# COMMUNICATION.net
KiCad netlist of a schematic drawn in Altium Designer
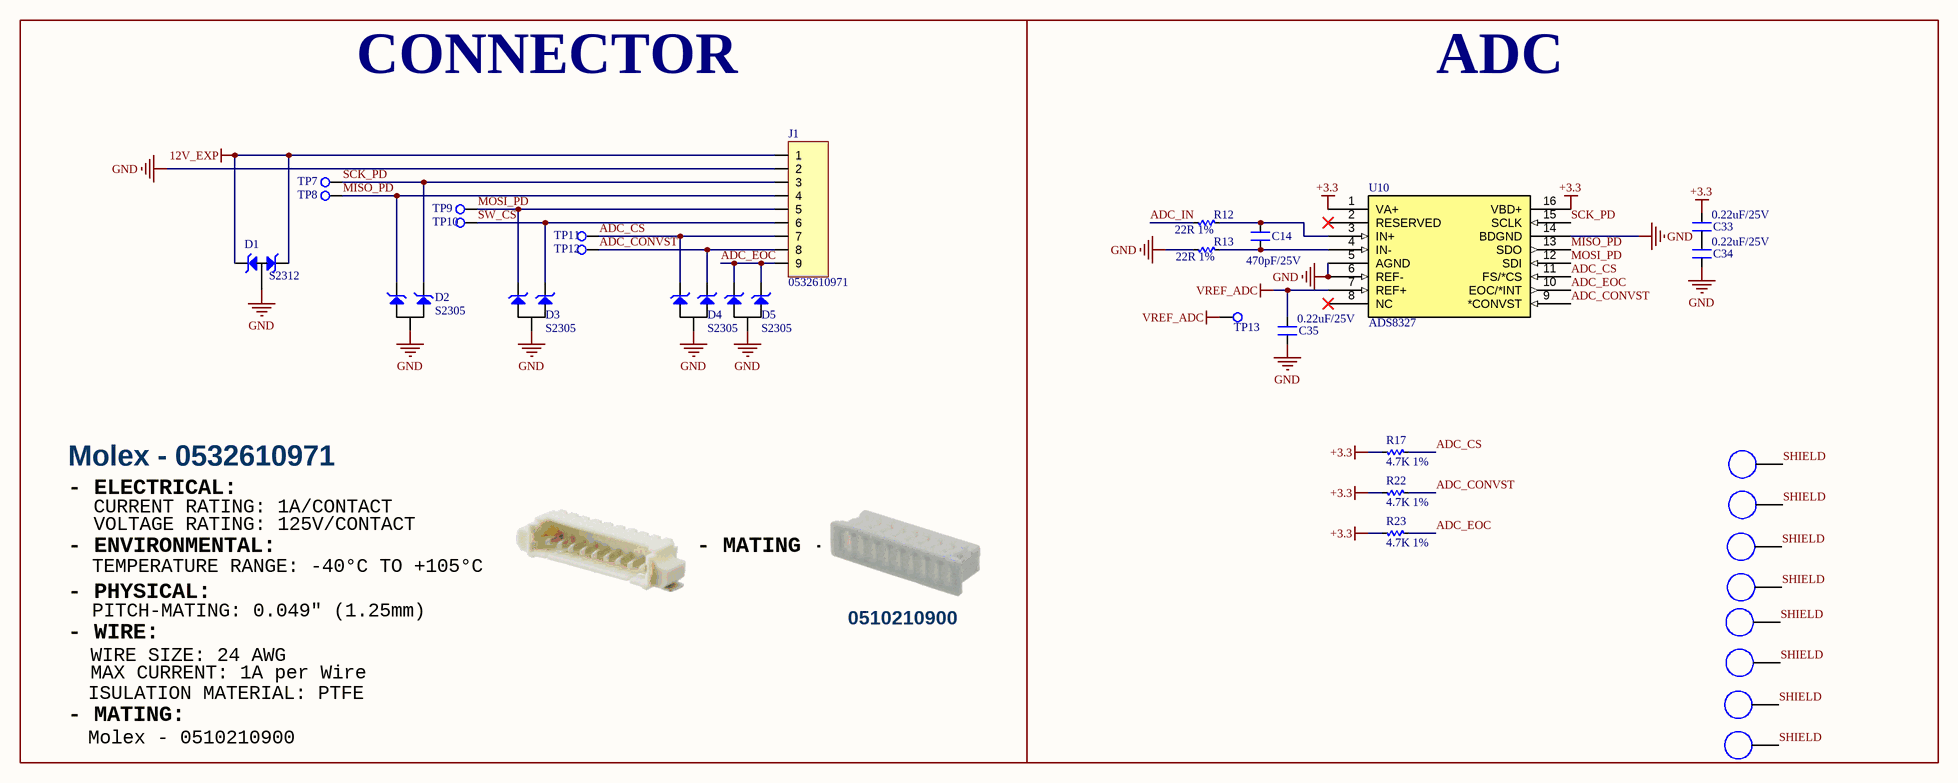
[diagram p0: COMMUNICATION.SchDoc]

(export (version "E")
  (design (tool "Eeschema 10.0.6"))
  (components
    (comp (ref "C14")
      (value "470pF/25V")
      (footprint "CN-SMD-0603")
      (description "0603")
      (libsource (lib "Capacitors") (part "CM"))
    )
    (comp (ref "C33")
      (value "0.22uF/25V")
      (footprint "CN-SMD-0603")
      (description "0603")
      (libsource (lib "Capacitors") (part "CM"))
    )
    (comp (ref "C34")
      (value "0.22uF/25V")
      (footprint "CN-SMD-0603")
      (description "0603")
      (libsource (lib "Capacitors") (part "CM"))
    )
    (comp (ref "C35")
      (value "0.22uF/25V")
      (footprint "CN-SMD-0603")
      (description "0603")
      (libsource (lib "Capacitors") (part "CM"))
    )
    (comp (ref "D1")
      (value "S2312")
      (footprint "SOT23-123")
      (description "TVS DIODE 12VWM 19VC SOT23, P/N:  S2312")
      (libsource (lib "Library") (part "S2315"))
    )
    (comp (ref "D2")
      (value "S2305")
      (footprint "SOT23-123")
      (description "TVS DIODE 5VWM 10.8VC SOT23, P/N:  \r\nS2305")
      (libsource (lib "Library") (part "S2303"))
    )
    (comp (ref "D3")
      (value "S2305")
      (footprint "SOT23-123")
      (description "TVS DIODE 5VWM 10.8VC SOT23, P/N:  \r\nS2305")
      (libsource (lib "Library") (part "S2303"))
    )
    (comp (ref "D4")
      (value "S2305")
      (footprint "SOT23-123")
      (description "TVS DIODE 5VWM 10.8VC SOT23, P/N:  \r\nS2305")
      (libsource (lib "Library") (part "S2303"))
    )
    (comp (ref "D5")
      (value "S2305")
      (footprint "SOT23-123")
      (description "TVS DIODE 5VWM 10.8VC SOT23, P/N:  \r\nS2305")
      (libsource (lib "Library") (part "S2303"))
    )
    (comp (ref "H1") (value "HOLD") (footprint "M3 - 6mm") (libsource (lib "Library_HUNG") (part "PAD_HOLD")))
    (comp (ref "H2") (value "HOLD") (footprint "M3 - 6mm") (libsource (lib "Library_HUNG") (part "PAD_HOLD")))
    (comp (ref "H3") (value "HOLD") (footprint "M3 - 6mm") (libsource (lib "Library_HUNG") (part "PAD_HOLD")))
    (comp (ref "H4") (value "HOLD") (footprint "M3 - 6mm") (libsource (lib "Library_HUNG") (part "PAD_HOLD")))
    (comp (ref "H5") (value "HOLD") (footprint "M3 - 6mm") (libsource (lib "Library_HUNG") (part "PAD_HOLD")))
    (comp (ref "H6") (value "HOLD") (footprint "M3 - 6mm") (libsource (lib "Library_HUNG") (part "PAD_HOLD")))
    (comp (ref "H7") (value "HOLD") (footprint "M3 - 6mm") (libsource (lib "Library_HUNG") (part "PAD_HOLD")))
    (comp (ref "H8") (value "HOLD") (footprint "M3 - 6mm") (libsource (lib "Library_HUNG") (part "PAD_HOLD")))
    (comp (ref "J1")
      (value "0532610971")
      (footprint "0532610971")
      (description "WR-PHD 2.54 mm Angled Socket Header")
      (fields
        (field (name "MANUFACTURER") "Würth Elektronik eiSos GmbH")
        (field (name "PARTNO") "613009143121")
        (field (name "CREATED BY") "Karrer Zheng")
      )
      (libsource (lib "Library") (part "JP9"))
    )
    (comp (ref "R12")
      (value "22R 1%")
      (footprint "RES-SMD-0603")
      (description "0603")
      (fields
        (field (name "MANUFACTURER") "Generic Components")
        (field (name "PUBLISHER") "Altium Hobart Technology Centre")
      )
      (libsource (lib "Library") (part "Res-SMD"))
    )
    (comp (ref "R13")
      (value "22R 1%")
      (footprint "RES-SMD-0603")
      (description "0603")
      (fields
        (field (name "MANUFACTURER") "Generic Components")
        (field (name "PUBLISHER") "Altium Hobart Technology Centre")
      )
      (libsource (lib "Library") (part "Res-SMD"))
    )
    (comp (ref "R17")
      (value "4.7K 1%")
      (footprint "RES-SMD-0603")
      (description "0603")
      (fields
        (field (name "MANUFACTURER") "Generic Components")
        (field (name "PUBLISHER") "Altium Hobart Technology Centre")
      )
      (libsource (lib "Library") (part "Res-SMD"))
    )
    (comp (ref "R22")
      (value "4.7K 1%")
      (footprint "RES-SMD-0603")
      (description "0603")
      (fields
        (field (name "MANUFACTURER") "Generic Components")
        (field (name "PUBLISHER") "Altium Hobart Technology Centre")
      )
      (libsource (lib "Library") (part "Res-SMD"))
    )
    (comp (ref "R23")
      (value "4.7K 1%")
      (footprint "RES-SMD-0603")
      (description "0603")
      (fields
        (field (name "MANUFACTURER") "Generic Components")
        (field (name "PUBLISHER") "Altium Hobart Technology Centre")
      )
      (libsource (lib "Library") (part "Res-SMD"))
    )
    (comp (ref "TP7")
      (value "Test_Point")
      (footprint "TESTPOINT")
      (libsource (lib "Library_HUNG") (part "Test_Point"))
    )
    (comp (ref "TP8")
      (value "Test_Point")
      (footprint "TESTPOINT")
      (libsource (lib "Library_HUNG") (part "Test_Point"))
    )
    (comp (ref "TP9")
      (value "Test_Point")
      (footprint "TESTPOINT")
      (libsource (lib "Library_HUNG") (part "Test_Point"))
    )
    (comp (ref "TP10")
      (value "Test_Point")
      (footprint "TESTPOINT")
      (libsource (lib "Library_HUNG") (part "Test_Point"))
    )
    (comp (ref "TP11")
      (value "Test_Point")
      (footprint "TESTPOINT")
      (libsource (lib "Library_HUNG") (part "Test_Point"))
    )
    (comp (ref "TP12")
      (value "Test_Point")
      (footprint "TESTPOINT")
      (libsource (lib "Library_HUNG") (part "Test_Point"))
    )
    (comp (ref "TP13")
      (value "Test_Point")
      (footprint "TESTPOINT")
      (libsource (lib "Library_HUNG") (part "Test_Point"))
    )
    (comp (ref "U10")
      (value "ADS8327")
      (footprint "TSSOP16")
      (description "IC ADC 16BIT SAR 16TSSOP")
      (libsource (lib "Library") (part "ADS8327"))
    )
  )
  (nets
    (net (code "1") (name "+3.3") (class "Default")
      (node (ref "C33") (pin "2") (pinfunction "2_2") (pintype "passive"))
      (node (ref "R17") (pin "2") (pinfunction "2_2") (pintype "passive"))
      (node (ref "R22") (pin "2") (pinfunction "2_2") (pintype "passive"))
      (node (ref "R23") (pin "2") (pinfunction "2_2") (pintype "passive"))
      (node (ref "U10") (pin "1") (pinfunction "VA+_1") (pintype "power_in"))
      (node (ref "U10") (pin "16") (pinfunction "VBD+_16") (pintype "power_in"))
    )
    (net (code "2") (name "/ADC_CONVST") (class "Default")
      (node (ref "D4") (pin "3") (pintype "passive"))
      (node (ref "J1") (pin "8") (pinfunction "8_8") (pintype "passive"))
      (node (ref "R22") (pin "1") (pinfunction "1_1") (pintype "passive"))
      (node (ref "TP12") (pin "1") (pintype "power_in"))
      (node (ref "U10") (pin "9") (pinfunction "*CONVST_9") (pintype "input"))
    )
    (net (code "3") (name "/ADC_CS") (class "Default")
      (node (ref "D4") (pin "1") (pintype "passive"))
      (node (ref "J1") (pin "7") (pinfunction "7_7") (pintype "passive"))
      (node (ref "R17") (pin "1") (pinfunction "1_1") (pintype "passive"))
      (node (ref "TP11") (pin "1") (pintype "power_in"))
      (node (ref "U10") (pin "11") (pinfunction "FS/*CS_11") (pintype "input"))
    )
    (net (code "4") (name "/ADC_EOC") (class "Default")
      (node (ref "D5") (pin "1") (pintype "passive"))
      (node (ref "D5") (pin "3") (pintype "passive"))
      (node (ref "J1") (pin "9") (pinfunction "9_9") (pintype "passive"))
      (node (ref "R23") (pin "1") (pinfunction "1_1") (pintype "passive"))
      (node (ref "U10") (pin "10") (pinfunction "EOC/*INT_10") (pintype "output"))
    )
    (net (code "5") (name "/ADC_IN") (class "Default")
      (node (ref "R12") (pin "2") (pinfunction "2_2") (pintype "passive"))
    )
    (net (code "6") (name "/MISO_PD") (class "Default")
      (node (ref "D2") (pin "3") (pintype "passive"))
      (node (ref "J1") (pin "4") (pinfunction "4_4") (pintype "passive"))
      (node (ref "TP8") (pin "1") (pintype "power_in"))
      (node (ref "U10") (pin "13") (pinfunction "SDO_13") (pintype "output"))
    )
    (net (code "7") (name "/MOSI_PD") (class "Default")
      (node (ref "D3") (pin "1") (pintype "passive"))
      (node (ref "J1") (pin "5") (pinfunction "5_5") (pintype "passive"))
      (node (ref "TP9") (pin "1") (pintype "power_in"))
      (node (ref "U10") (pin "12") (pinfunction "SDI_12") (pintype "input"))
    )
    (net (code "8") (name "/SCK_PD") (class "Default")
      (node (ref "D2") (pin "1") (pintype "passive"))
      (node (ref "J1") (pin "3") (pinfunction "3_3") (pintype "passive"))
      (node (ref "TP7") (pin "1") (pintype "power_in"))
      (node (ref "U10") (pin "15") (pinfunction "SCLK_15") (pintype "input"))
    )
    (net (code "9") (name "/SHIELD") (class "Default")
      (node (ref "H1") (pin "1") (pintype "power_in"))
      (node (ref "H2") (pin "1") (pintype "power_in"))
      (node (ref "H3") (pin "1") (pintype "power_in"))
      (node (ref "H4") (pin "1") (pintype "power_in"))
      (node (ref "H5") (pin "1") (pintype "power_in"))
      (node (ref "H6") (pin "1") (pintype "power_in"))
      (node (ref "H7") (pin "1") (pintype "power_in"))
      (node (ref "H8") (pin "1") (pintype "power_in"))
    )
    (net (code "10") (name "/SW_CS") (class "Default")
      (node (ref "D3") (pin "3") (pintype "passive"))
      (node (ref "J1") (pin "6") (pinfunction "6_6") (pintype "passive"))
      (node (ref "TP10") (pin "1") (pintype "power_in"))
    )
    (net (code "11") (name "12V_EXP") (class "Default")
      (node (ref "D1") (pin "1") (pintype "passive"))
      (node (ref "D1") (pin "3") (pintype "passive"))
      (node (ref "J1") (pin "1") (pinfunction "1_1") (pintype "passive"))
    )
    (net (code "12") (name "GND") (class "Default")
      (node (ref "C34") (pin "1") (pinfunction "1_1") (pintype "passive"))
      (node (ref "C35") (pin "1") (pinfunction "1_1") (pintype "passive"))
      (node (ref "D1") (pin "2") (pintype "passive"))
      (node (ref "D2") (pin "2") (pintype "passive"))
      (node (ref "D3") (pin "2") (pintype "passive"))
      (node (ref "D4") (pin "2") (pintype "passive"))
      (node (ref "D5") (pin "2") (pintype "passive"))
      (node (ref "J1") (pin "2") (pinfunction "2_2") (pintype "passive"))
      (node (ref "R13") (pin "2") (pinfunction "2_2") (pintype "passive"))
      (node (ref "U10") (pin "14") (pinfunction "BDGND_14") (pintype "power_in"))
      (node (ref "U10") (pin "5") (pinfunction "AGND_5") (pintype "power_in"))
      (node (ref "U10") (pin "6") (pinfunction "REF-_6") (pintype "input"))
    )
    (net (code "13") (name "Net-(C33-Pad1)") (class "Default")
      (node (ref "C33") (pin "1") (pinfunction "1_1") (pintype "passive"))
      (node (ref "C34") (pin "2") (pinfunction "2_2") (pintype "passive"))
    )
    (net (code "14") (name "Net-(U10-IN+)") (class "Default")
      (node (ref "C14") (pin "2") (pinfunction "2_2") (pintype "passive"))
      (node (ref "R12") (pin "1") (pinfunction "1_1") (pintype "passive"))
      (node (ref "U10") (pin "3") (pinfunction "IN+_3") (pintype "input"))
    )
    (net (code "15") (name "Net-(U10-IN-)") (class "Default")
      (node (ref "C14") (pin "1") (pinfunction "1_1") (pintype "passive"))
      (node (ref "R13") (pin "1") (pinfunction "1_1") (pintype "passive"))
      (node (ref "U10") (pin "4") (pinfunction "IN-_4") (pintype "input"))
    )
    (net (code "16") (name "VREF_ADC") (class "Default")
      (node (ref "C35") (pin "2") (pinfunction "2_2") (pintype "passive"))
      (node (ref "TP13") (pin "1") (pintype "power_in"))
      (node (ref "U10") (pin "7") (pinfunction "REF+_7") (pintype "input"))
    )
    (net (code "17") (name "unconnected-(U10-NC-Pad8)") (class "Default")
      (node (ref "U10") (pin "8") (pinfunction "NC_8") (pintype "passive+no_connect"))
    )
    (net (code "18") (name "unconnected-(U10-RESERVED-Pad2)") (class "Default")
      (node (ref "U10") (pin "2") (pinfunction "RESERVED_2") (pintype "passive+no_connect"))
    )
  )
)
